# Nav_Solenoid_IO.net
KiCad netlist of a schematic drawn in Altium Designer
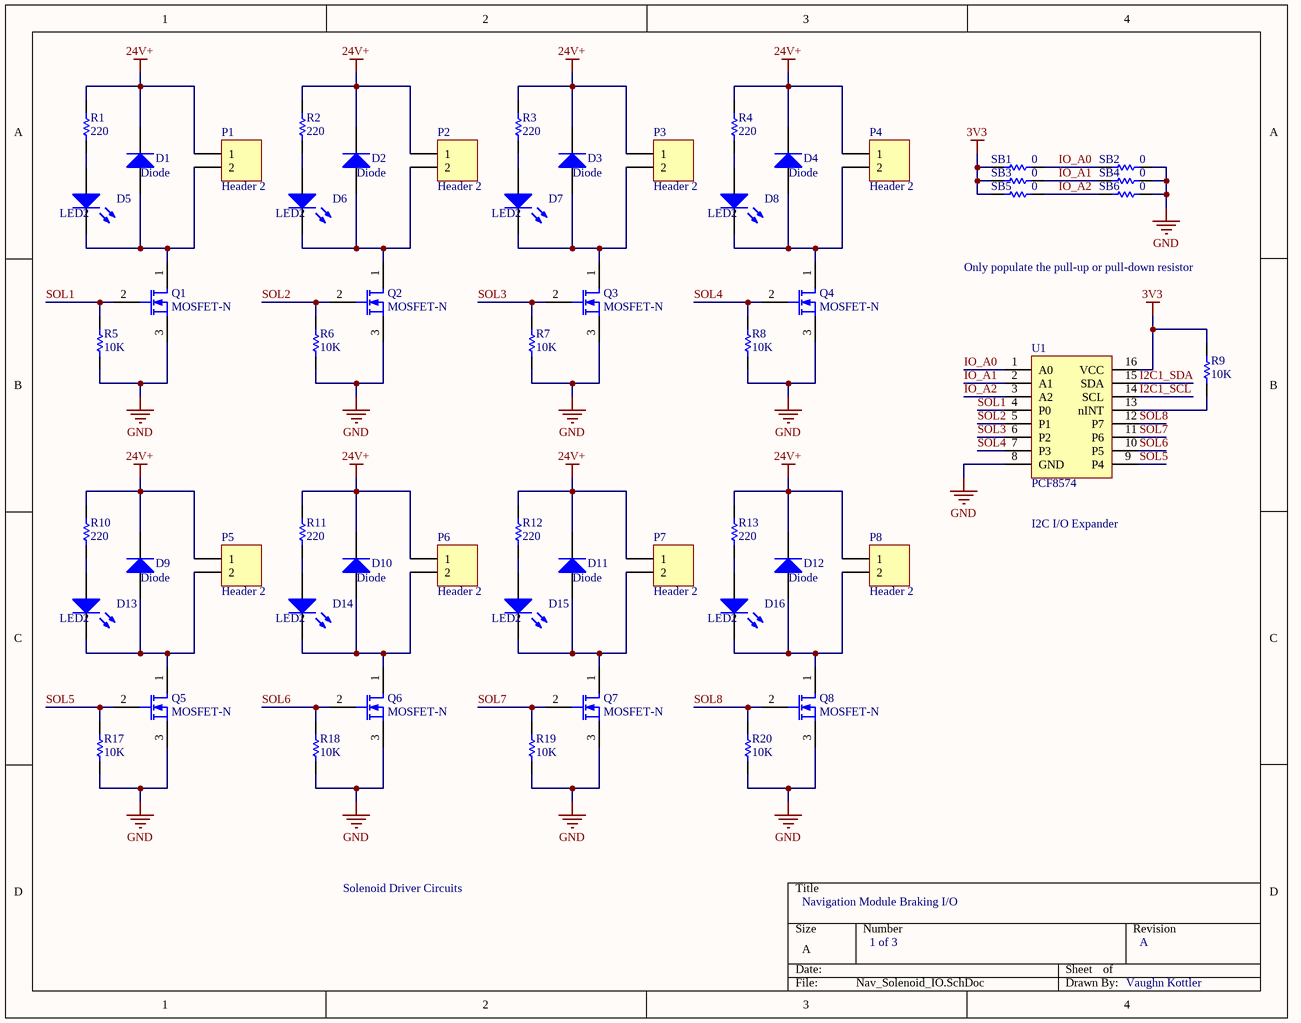
[diagram p0: Nav_Solenoid_IO.SchDoc]

(export (version "E")
  (design (tool "Eeschema 10.0.6"))
  (components
    (comp (ref "D1")
      (value "Diode")
      (footprint "DIODE_SMC")
      (description "Default Diode")
      (fields (field (name "PUBLISHER") "Altium Limited"))
      (libsource (lib "Miscellaneous Devices") (part "Diode"))
    )
    (comp (ref "D2")
      (value "Diode")
      (footprint "DIODE_SMC")
      (description "Default Diode")
      (fields (field (name "PUBLISHER") "Altium Limited"))
      (libsource (lib "Miscellaneous Devices") (part "Diode"))
    )
    (comp (ref "D3")
      (value "Diode")
      (footprint "DIODE_SMC")
      (description "Default Diode")
      (fields (field (name "PUBLISHER") "Altium Limited"))
      (libsource (lib "Miscellaneous Devices") (part "Diode"))
    )
    (comp (ref "D4")
      (value "Diode")
      (footprint "DIODE_SMC")
      (description "Default Diode")
      (fields (field (name "PUBLISHER") "Altium Limited"))
      (libsource (lib "Miscellaneous Devices") (part "Diode"))
    )
    (comp (ref "D5")
      (value "LED2")
      (footprint "3.2X1.6X1.1")
      (description "Typical RED, GREEN, YELLOW, AMBER GaAs LED")
      (fields (field (name "PUBLISHER") "Altium Limited"))
      (libsource (lib "Miscellaneous Devices") (part "LED2"))
    )
    (comp (ref "D6")
      (value "LED2")
      (footprint "3.2X1.6X1.1")
      (description "Typical RED, GREEN, YELLOW, AMBER GaAs LED")
      (fields (field (name "PUBLISHER") "Altium Limited"))
      (libsource (lib "Miscellaneous Devices") (part "LED2"))
    )
    (comp (ref "D7")
      (value "LED2")
      (footprint "3.2X1.6X1.1")
      (description "Typical RED, GREEN, YELLOW, AMBER GaAs LED")
      (fields (field (name "PUBLISHER") "Altium Limited"))
      (libsource (lib "Miscellaneous Devices") (part "LED2"))
    )
    (comp (ref "D8")
      (value "LED2")
      (footprint "3.2X1.6X1.1")
      (description "Typical RED, GREEN, YELLOW, AMBER GaAs LED")
      (fields (field (name "PUBLISHER") "Altium Limited"))
      (libsource (lib "Miscellaneous Devices") (part "LED2"))
    )
    (comp (ref "D9")
      (value "Diode")
      (footprint "DIODE_SMC")
      (description "Default Diode")
      (fields (field (name "PUBLISHER") "Altium Limited"))
      (libsource (lib "Miscellaneous Devices") (part "Diode"))
    )
    (comp (ref "D10")
      (value "Diode")
      (footprint "DIODE_SMC")
      (description "Default Diode")
      (fields (field (name "PUBLISHER") "Altium Limited"))
      (libsource (lib "Miscellaneous Devices") (part "Diode"))
    )
    (comp (ref "D11")
      (value "Diode")
      (footprint "DIODE_SMC")
      (description "Default Diode")
      (fields (field (name "PUBLISHER") "Altium Limited"))
      (libsource (lib "Miscellaneous Devices") (part "Diode"))
    )
    (comp (ref "D12")
      (value "Diode")
      (footprint "DIODE_SMC")
      (description "Default Diode")
      (fields (field (name "PUBLISHER") "Altium Limited"))
      (libsource (lib "Miscellaneous Devices") (part "Diode"))
    )
    (comp (ref "D13")
      (value "LED2")
      (footprint "3.2X1.6X1.1")
      (description "Typical RED, GREEN, YELLOW, AMBER GaAs LED")
      (fields (field (name "PUBLISHER") "Altium Limited"))
      (libsource (lib "Miscellaneous Devices") (part "LED2"))
    )
    (comp (ref "D14")
      (value "LED2")
      (footprint "3.2X1.6X1.1")
      (description "Typical RED, GREEN, YELLOW, AMBER GaAs LED")
      (fields (field (name "PUBLISHER") "Altium Limited"))
      (libsource (lib "Miscellaneous Devices") (part "LED2"))
    )
    (comp (ref "D15")
      (value "LED2")
      (footprint "3.2X1.6X1.1")
      (description "Typical RED, GREEN, YELLOW, AMBER GaAs LED")
      (fields (field (name "PUBLISHER") "Altium Limited"))
      (libsource (lib "Miscellaneous Devices") (part "LED2"))
    )
    (comp (ref "D16")
      (value "LED2")
      (footprint "3.2X1.6X1.1")
      (description "Typical RED, GREEN, YELLOW, AMBER GaAs LED")
      (fields (field (name "PUBLISHER") "Altium Limited"))
      (libsource (lib "Miscellaneous Devices") (part "LED2"))
    )
    (comp (ref "P1")
      (value "Header 2")
      (footprint "2POS TERM BLOCK")
      (description "Header, 2-Pin")
      (fields (field (name "PUBLISHER") "Altium Limited"))
      (libsource (lib "Miscellaneous Connectors") (part "Header 2"))
    )
    (comp (ref "P2")
      (value "Header 2")
      (footprint "2POS TERM BLOCK")
      (description "Header, 2-Pin")
      (fields (field (name "PUBLISHER") "Altium Limited"))
      (libsource (lib "Miscellaneous Connectors") (part "Header 2"))
    )
    (comp (ref "P3")
      (value "Header 2")
      (footprint "2POS TERM BLOCK")
      (description "Header, 2-Pin")
      (fields (field (name "PUBLISHER") "Altium Limited"))
      (libsource (lib "Miscellaneous Connectors") (part "Header 2"))
    )
    (comp (ref "P4")
      (value "Header 2")
      (footprint "2POS TERM BLOCK")
      (description "Header, 2-Pin")
      (fields (field (name "PUBLISHER") "Altium Limited"))
      (libsource (lib "Miscellaneous Connectors") (part "Header 2"))
    )
    (comp (ref "P5")
      (value "Header 2")
      (footprint "2POS TERM BLOCK")
      (description "Header, 2-Pin")
      (fields (field (name "PUBLISHER") "Altium Limited"))
      (libsource (lib "Miscellaneous Connectors") (part "Header 2"))
    )
    (comp (ref "P6")
      (value "Header 2")
      (footprint "2POS TERM BLOCK")
      (description "Header, 2-Pin")
      (fields (field (name "PUBLISHER") "Altium Limited"))
      (libsource (lib "Miscellaneous Connectors") (part "Header 2"))
    )
    (comp (ref "P7")
      (value "Header 2")
      (footprint "2POS TERM BLOCK")
      (description "Header, 2-Pin")
      (fields (field (name "PUBLISHER") "Altium Limited"))
      (libsource (lib "Miscellaneous Connectors") (part "Header 2"))
    )
    (comp (ref "P8")
      (value "Header 2")
      (footprint "2POS TERM BLOCK")
      (description "Header, 2-Pin")
      (fields (field (name "PUBLISHER") "Altium Limited"))
      (libsource (lib "Miscellaneous Connectors") (part "Header 2"))
    )
    (comp (ref "Q1")
      (value "MOSFET-N")
      (footprint "SOT23_N")
      (description "N-Channel MOSFET")
      (fields (field (name "PUBLISHER") "Altium Limited"))
      (libsource (lib "Miscellaneous Devices") (part "MOSFET-N"))
    )
    (comp (ref "Q2")
      (value "MOSFET-N")
      (footprint "SOT23_N")
      (description "N-Channel MOSFET")
      (fields (field (name "PUBLISHER") "Altium Limited"))
      (libsource (lib "Miscellaneous Devices") (part "MOSFET-N"))
    )
    (comp (ref "Q3")
      (value "MOSFET-N")
      (footprint "SOT23_N")
      (description "N-Channel MOSFET")
      (fields (field (name "PUBLISHER") "Altium Limited"))
      (libsource (lib "Miscellaneous Devices") (part "MOSFET-N"))
    )
    (comp (ref "Q4")
      (value "MOSFET-N")
      (footprint "SOT23_N")
      (description "N-Channel MOSFET")
      (fields (field (name "PUBLISHER") "Altium Limited"))
      (libsource (lib "Miscellaneous Devices") (part "MOSFET-N"))
    )
    (comp (ref "Q5")
      (value "MOSFET-N")
      (footprint "SOT23_N")
      (description "N-Channel MOSFET")
      (fields (field (name "PUBLISHER") "Altium Limited"))
      (libsource (lib "Miscellaneous Devices") (part "MOSFET-N"))
    )
    (comp (ref "Q6")
      (value "MOSFET-N")
      (footprint "SOT23_N")
      (description "N-Channel MOSFET")
      (fields (field (name "PUBLISHER") "Altium Limited"))
      (libsource (lib "Miscellaneous Devices") (part "MOSFET-N"))
    )
    (comp (ref "Q7")
      (value "MOSFET-N")
      (footprint "SOT23_N")
      (description "N-Channel MOSFET")
      (fields (field (name "PUBLISHER") "Altium Limited"))
      (libsource (lib "Miscellaneous Devices") (part "MOSFET-N"))
    )
    (comp (ref "Q8")
      (value "MOSFET-N")
      (footprint "SOT23_N")
      (description "N-Channel MOSFET")
      (fields (field (name "PUBLISHER") "Altium Limited"))
      (libsource (lib "Miscellaneous Devices") (part "MOSFET-N"))
    )
    (comp (ref "R1")
      (value "220")
      (footprint "6-0805_M")
      (description "Resistor")
      (fields (field (name "Comment") "Res1") (field (name "PUBLISHER") "Altium Limited"))
      (libsource (lib "Miscellaneous Devices") (part "Res1"))
    )
    (comp (ref "R2")
      (value "220")
      (footprint "6-0805_M")
      (description "Resistor")
      (fields (field (name "Comment") "Res1") (field (name "PUBLISHER") "Altium Limited"))
      (libsource (lib "Miscellaneous Devices") (part "Res1"))
    )
    (comp (ref "R3")
      (value "220")
      (footprint "6-0805_M")
      (description "Resistor")
      (fields (field (name "Comment") "Res1") (field (name "PUBLISHER") "Altium Limited"))
      (libsource (lib "Miscellaneous Devices") (part "Res1"))
    )
    (comp (ref "R4")
      (value "220")
      (footprint "6-0805_M")
      (description "Resistor")
      (fields (field (name "Comment") "Res1") (field (name "PUBLISHER") "Altium Limited"))
      (libsource (lib "Miscellaneous Devices") (part "Res1"))
    )
    (comp (ref "R5")
      (value "10K")
      (footprint "6-0805_M")
      (description "Resistor")
      (fields (field (name "Comment") "Res1") (field (name "PUBLISHER") "Altium Limited"))
      (libsource (lib "Miscellaneous Devices") (part "Res1"))
    )
    (comp (ref "R6")
      (value "10K")
      (footprint "6-0805_M")
      (description "Resistor")
      (fields (field (name "Comment") "Res1") (field (name "PUBLISHER") "Altium Limited"))
      (libsource (lib "Miscellaneous Devices") (part "Res1"))
    )
    (comp (ref "R7")
      (value "10K")
      (footprint "6-0805_M")
      (description "Resistor")
      (fields (field (name "Comment") "Res1") (field (name "PUBLISHER") "Altium Limited"))
      (libsource (lib "Miscellaneous Devices") (part "Res1"))
    )
    (comp (ref "R8")
      (value "10K")
      (footprint "6-0805_M")
      (description "Resistor")
      (fields (field (name "Comment") "Res1") (field (name "PUBLISHER") "Altium Limited"))
      (libsource (lib "Miscellaneous Devices") (part "Res1"))
    )
    (comp (ref "R9")
      (value "10K")
      (footprint "6-0805_M")
      (description "Resistor")
      (fields (field (name "Comment") "Res1") (field (name "PUBLISHER") "Altium Limited"))
      (libsource (lib "Miscellaneous Devices") (part "Res1"))
    )
    (comp (ref "R10")
      (value "220")
      (footprint "6-0805_M")
      (description "Resistor")
      (fields (field (name "Comment") "Res1") (field (name "PUBLISHER") "Altium Limited"))
      (libsource (lib "Miscellaneous Devices") (part "Res1"))
    )
    (comp (ref "R11")
      (value "220")
      (footprint "6-0805_M")
      (description "Resistor")
      (fields (field (name "Comment") "Res1") (field (name "PUBLISHER") "Altium Limited"))
      (libsource (lib "Miscellaneous Devices") (part "Res1"))
    )
    (comp (ref "R12")
      (value "220")
      (footprint "6-0805_M")
      (description "Resistor")
      (fields (field (name "Comment") "Res1") (field (name "PUBLISHER") "Altium Limited"))
      (libsource (lib "Miscellaneous Devices") (part "Res1"))
    )
    (comp (ref "R13")
      (value "220")
      (footprint "6-0805_M")
      (description "Resistor")
      (fields (field (name "Comment") "Res1") (field (name "PUBLISHER") "Altium Limited"))
      (libsource (lib "Miscellaneous Devices") (part "Res1"))
    )
    (comp (ref "R17")
      (value "10K")
      (footprint "6-0805_M")
      (description "Resistor")
      (fields (field (name "Comment") "Res1") (field (name "PUBLISHER") "Altium Limited"))
      (libsource (lib "Miscellaneous Devices") (part "Res1"))
    )
    (comp (ref "R18")
      (value "10K")
      (footprint "6-0805_M")
      (description "Resistor")
      (fields (field (name "Comment") "Res1") (field (name "PUBLISHER") "Altium Limited"))
      (libsource (lib "Miscellaneous Devices") (part "Res1"))
    )
    (comp (ref "R19")
      (value "10K")
      (footprint "6-0805_M")
      (description "Resistor")
      (fields (field (name "Comment") "Res1") (field (name "PUBLISHER") "Altium Limited"))
      (libsource (lib "Miscellaneous Devices") (part "Res1"))
    )
    (comp (ref "R20")
      (value "10K")
      (footprint "6-0805_M")
      (description "Resistor")
      (fields (field (name "Comment") "Res1") (field (name "PUBLISHER") "Altium Limited"))
      (libsource (lib "Miscellaneous Devices") (part "Res1"))
    )
    (comp (ref "SB1")
      (value "0")
      (footprint "6-0805_M")
      (description "Resistor")
      (fields (field (name "Comment") "Res1") (field (name "PUBLISHER") "Altium Limited"))
      (libsource (lib "Miscellaneous Devices") (part "Res1"))
    )
    (comp (ref "SB2")
      (value "0")
      (footprint "6-0805_M")
      (description "Resistor")
      (fields (field (name "Comment") "Res1") (field (name "PUBLISHER") "Altium Limited"))
      (libsource (lib "Miscellaneous Devices") (part "Res1"))
    )
    (comp (ref "SB3")
      (value "0")
      (footprint "6-0805_M")
      (description "Resistor")
      (fields (field (name "Comment") "Res1") (field (name "PUBLISHER") "Altium Limited"))
      (libsource (lib "Miscellaneous Devices") (part "Res1"))
    )
    (comp (ref "SB4")
      (value "0")
      (footprint "6-0805_M")
      (description "Resistor")
      (fields (field (name "Comment") "Res1") (field (name "PUBLISHER") "Altium Limited"))
      (libsource (lib "Miscellaneous Devices") (part "Res1"))
    )
    (comp (ref "SB5")
      (value "0")
      (footprint "6-0805_M")
      (description "Resistor")
      (fields (field (name "Comment") "Res1") (field (name "PUBLISHER") "Altium Limited"))
      (libsource (lib "Miscellaneous Devices") (part "Res1"))
    )
    (comp (ref "SB6")
      (value "0")
      (footprint "6-0805_M")
      (description "Resistor")
      (fields (field (name "Comment") "Res1") (field (name "PUBLISHER") "Altium Limited"))
      (libsource (lib "Miscellaneous Devices") (part "Res1"))
    )
    (comp (ref "U1")
      (value "PCF8574")
      (footprint "16-SOIC")
      (description "I2C I/O Expander")
      (libsource (lib "ic") (part "PCF8574"))
    )
  )
  (nets
    (net (code "1") (name "/I2C1_SCL") (class "Default")
      (node (ref "U1") (pin "14") (pinfunction "SCL_14") (pintype "passive"))
    )
    (net (code "2") (name "/I2C1_SDA") (class "Default")
      (node (ref "U1") (pin "15") (pinfunction "SDA_15") (pintype "passive"))
    )
    (net (code "3") (name "/IO_A0") (class "Default")
      (node (ref "SB1") (pin "1") (pinfunction "1_1") (pintype "passive"))
      (node (ref "SB2") (pin "2") (pinfunction "2_2") (pintype "passive"))
      (node (ref "U1") (pin "1") (pinfunction "A0_1") (pintype "passive"))
    )
    (net (code "4") (name "/IO_A1") (class "Default")
      (node (ref "SB3") (pin "1") (pinfunction "1_1") (pintype "passive"))
      (node (ref "SB4") (pin "2") (pinfunction "2_2") (pintype "passive"))
      (node (ref "U1") (pin "2") (pinfunction "A1_2") (pintype "passive"))
    )
    (net (code "5") (name "/IO_A2") (class "Default")
      (node (ref "SB5") (pin "1") (pinfunction "1_1") (pintype "passive"))
      (node (ref "SB6") (pin "2") (pinfunction "2_2") (pintype "passive"))
      (node (ref "U1") (pin "3") (pinfunction "A2_3") (pintype "passive"))
    )
    (net (code "6") (name "/SOL1") (class "Default")
      (node (ref "Q1") (pin "2") (pinfunction "G_2") (pintype "passive"))
      (node (ref "R5") (pin "2") (pinfunction "2_2") (pintype "passive"))
      (node (ref "U1") (pin "4") (pinfunction "P0_4") (pintype "passive"))
    )
    (net (code "7") (name "/SOL2") (class "Default")
      (node (ref "Q2") (pin "2") (pinfunction "G_2") (pintype "passive"))
      (node (ref "R6") (pin "2") (pinfunction "2_2") (pintype "passive"))
      (node (ref "U1") (pin "5") (pinfunction "P1_5") (pintype "passive"))
    )
    (net (code "8") (name "/SOL3") (class "Default")
      (node (ref "Q3") (pin "2") (pinfunction "G_2") (pintype "passive"))
      (node (ref "R7") (pin "2") (pinfunction "2_2") (pintype "passive"))
      (node (ref "U1") (pin "6") (pinfunction "P2_6") (pintype "passive"))
    )
    (net (code "9") (name "/SOL4") (class "Default")
      (node (ref "Q4") (pin "2") (pinfunction "G_2") (pintype "passive"))
      (node (ref "R8") (pin "2") (pinfunction "2_2") (pintype "passive"))
      (node (ref "U1") (pin "7") (pinfunction "P3_7") (pintype "passive"))
    )
    (net (code "10") (name "/SOL5") (class "Default")
      (node (ref "Q5") (pin "2") (pinfunction "G_2") (pintype "passive"))
      (node (ref "R17") (pin "2") (pinfunction "2_2") (pintype "passive"))
      (node (ref "U1") (pin "9") (pinfunction "P4_9") (pintype "passive"))
    )
    (net (code "11") (name "/SOL6") (class "Default")
      (node (ref "Q6") (pin "2") (pinfunction "G_2") (pintype "passive"))
      (node (ref "R18") (pin "2") (pinfunction "2_2") (pintype "passive"))
      (node (ref "U1") (pin "10") (pinfunction "P5_10") (pintype "passive"))
    )
    (net (code "12") (name "/SOL7") (class "Default")
      (node (ref "Q7") (pin "2") (pinfunction "G_2") (pintype "passive"))
      (node (ref "R19") (pin "2") (pinfunction "2_2") (pintype "passive"))
      (node (ref "U1") (pin "11") (pinfunction "P6_11") (pintype "passive"))
    )
    (net (code "13") (name "/SOL8") (class "Default")
      (node (ref "Q8") (pin "2") (pinfunction "G_2") (pintype "passive"))
      (node (ref "R20") (pin "2") (pinfunction "2_2") (pintype "passive"))
      (node (ref "U1") (pin "12") (pinfunction "P7_12") (pintype "passive"))
    )
    (net (code "14") (name "3V3") (class "Default")
      (node (ref "R9") (pin "2") (pinfunction "2_2") (pintype "passive"))
      (node (ref "SB1") (pin "2") (pinfunction "2_2") (pintype "passive"))
      (node (ref "SB3") (pin "2") (pinfunction "2_2") (pintype "passive"))
      (node (ref "SB5") (pin "2") (pinfunction "2_2") (pintype "passive"))
      (node (ref "U1") (pin "16") (pinfunction "VCC_16") (pintype "passive"))
    )
    (net (code "15") (name "24V+") (class "Default")
      (node (ref "D1") (pin "2") (pinfunction "K_2") (pintype "passive"))
      (node (ref "D10") (pin "2") (pinfunction "K_2") (pintype "passive"))
      (node (ref "D11") (pin "2") (pinfunction "K_2") (pintype "passive"))
      (node (ref "D12") (pin "2") (pinfunction "K_2") (pintype "passive"))
      (node (ref "D2") (pin "2") (pinfunction "K_2") (pintype "passive"))
      (node (ref "D3") (pin "2") (pinfunction "K_2") (pintype "passive"))
      (node (ref "D4") (pin "2") (pinfunction "K_2") (pintype "passive"))
      (node (ref "D9") (pin "2") (pinfunction "K_2") (pintype "passive"))
      (node (ref "P1") (pin "1") (pinfunction "1_1") (pintype "passive"))
      (node (ref "P2") (pin "1") (pinfunction "1_1") (pintype "passive"))
      (node (ref "P3") (pin "1") (pinfunction "1_1") (pintype "passive"))
      (node (ref "P4") (pin "1") (pinfunction "1_1") (pintype "passive"))
      (node (ref "P5") (pin "1") (pinfunction "1_1") (pintype "passive"))
      (node (ref "P6") (pin "1") (pinfunction "1_1") (pintype "passive"))
      (node (ref "P7") (pin "1") (pinfunction "1_1") (pintype "passive"))
      (node (ref "P8") (pin "1") (pinfunction "1_1") (pintype "passive"))
      (node (ref "R1") (pin "2") (pinfunction "2_2") (pintype "passive"))
      (node (ref "R10") (pin "2") (pinfunction "2_2") (pintype "passive"))
      (node (ref "R11") (pin "2") (pinfunction "2_2") (pintype "passive"))
      (node (ref "R12") (pin "2") (pinfunction "2_2") (pintype "passive"))
      (node (ref "R13") (pin "2") (pinfunction "2_2") (pintype "passive"))
      (node (ref "R2") (pin "2") (pinfunction "2_2") (pintype "passive"))
      (node (ref "R3") (pin "2") (pinfunction "2_2") (pintype "passive"))
      (node (ref "R4") (pin "2") (pinfunction "2_2") (pintype "passive"))
    )
    (net (code "16") (name "GND") (class "Default")
      (node (ref "Q1") (pin "3") (pinfunction "S_3") (pintype "passive"))
      (node (ref "Q2") (pin "3") (pinfunction "S_3") (pintype "passive"))
      (node (ref "Q3") (pin "3") (pinfunction "S_3") (pintype "passive"))
      (node (ref "Q4") (pin "3") (pinfunction "S_3") (pintype "passive"))
      (node (ref "Q5") (pin "3") (pinfunction "S_3") (pintype "passive"))
      (node (ref "Q6") (pin "3") (pinfunction "S_3") (pintype "passive"))
      (node (ref "Q7") (pin "3") (pinfunction "S_3") (pintype "passive"))
      (node (ref "Q8") (pin "3") (pinfunction "S_3") (pintype "passive"))
      (node (ref "R17") (pin "1") (pinfunction "1_1") (pintype "passive"))
      (node (ref "R18") (pin "1") (pinfunction "1_1") (pintype "passive"))
      (node (ref "R19") (pin "1") (pinfunction "1_1") (pintype "passive"))
      (node (ref "R20") (pin "1") (pinfunction "1_1") (pintype "passive"))
      (node (ref "R5") (pin "1") (pinfunction "1_1") (pintype "passive"))
      (node (ref "R6") (pin "1") (pinfunction "1_1") (pintype "passive"))
      (node (ref "R7") (pin "1") (pinfunction "1_1") (pintype "passive"))
      (node (ref "R8") (pin "1") (pinfunction "1_1") (pintype "passive"))
      (node (ref "SB2") (pin "1") (pinfunction "1_1") (pintype "passive"))
      (node (ref "SB4") (pin "1") (pinfunction "1_1") (pintype "passive"))
      (node (ref "SB6") (pin "1") (pinfunction "1_1") (pintype "passive"))
      (node (ref "U1") (pin "8") (pinfunction "GND_8") (pintype "passive"))
    )
    (net (code "17") (name "Net-(D1-A)") (class "Default")
      (node (ref "D1") (pin "1") (pinfunction "A_1") (pintype "passive"))
      (node (ref "D5") (pin "2") (pinfunction "K_2") (pintype "passive"))
      (node (ref "P1") (pin "2") (pinfunction "2_2") (pintype "passive"))
      (node (ref "Q1") (pin "1") (pinfunction "D_1") (pintype "passive"))
    )
    (net (code "18") (name "Net-(D2-A)") (class "Default")
      (node (ref "D2") (pin "1") (pinfunction "A_1") (pintype "passive"))
      (node (ref "D6") (pin "2") (pinfunction "K_2") (pintype "passive"))
      (node (ref "P2") (pin "2") (pinfunction "2_2") (pintype "passive"))
      (node (ref "Q2") (pin "1") (pinfunction "D_1") (pintype "passive"))
    )
    (net (code "19") (name "Net-(D3-A)") (class "Default")
      (node (ref "D3") (pin "1") (pinfunction "A_1") (pintype "passive"))
      (node (ref "D7") (pin "2") (pinfunction "K_2") (pintype "passive"))
      (node (ref "P3") (pin "2") (pinfunction "2_2") (pintype "passive"))
      (node (ref "Q3") (pin "1") (pinfunction "D_1") (pintype "passive"))
    )
    (net (code "20") (name "Net-(D4-A)") (class "Default")
      (node (ref "D4") (pin "1") (pinfunction "A_1") (pintype "passive"))
      (node (ref "D8") (pin "2") (pinfunction "K_2") (pintype "passive"))
      (node (ref "P4") (pin "2") (pinfunction "2_2") (pintype "passive"))
      (node (ref "Q4") (pin "1") (pinfunction "D_1") (pintype "passive"))
    )
    (net (code "21") (name "Net-(D5-A)") (class "Default")
      (node (ref "D5") (pin "1") (pinfunction "A_1") (pintype "passive"))
      (node (ref "R1") (pin "1") (pinfunction "1_1") (pintype "passive"))
    )
    (net (code "22") (name "Net-(D6-A)") (class "Default")
      (node (ref "D6") (pin "1") (pinfunction "A_1") (pintype "passive"))
      (node (ref "R2") (pin "1") (pinfunction "1_1") (pintype "passive"))
    )
    (net (code "23") (name "Net-(D7-A)") (class "Default")
      (node (ref "D7") (pin "1") (pinfunction "A_1") (pintype "passive"))
      (node (ref "R3") (pin "1") (pinfunction "1_1") (pintype "passive"))
    )
    (net (code "24") (name "Net-(D8-A)") (class "Default")
      (node (ref "D8") (pin "1") (pinfunction "A_1") (pintype "passive"))
      (node (ref "R4") (pin "1") (pinfunction "1_1") (pintype "passive"))
    )
    (net (code "25") (name "Net-(D10-A)") (class "Default")
      (node (ref "D10") (pin "1") (pinfunction "A_1") (pintype "passive"))
      (node (ref "D14") (pin "2") (pinfunction "K_2") (pintype "passive"))
      (node (ref "P6") (pin "2") (pinfunction "2_2") (pintype "passive"))
      (node (ref "Q6") (pin "1") (pinfunction "D_1") (pintype "passive"))
    )
    (net (code "26") (name "Net-(D11-A)") (class "Default")
      (node (ref "D11") (pin "1") (pinfunction "A_1") (pintype "passive"))
      (node (ref "D15") (pin "2") (pinfunction "K_2") (pintype "passive"))
      (node (ref "P7") (pin "2") (pinfunction "2_2") (pintype "passive"))
      (node (ref "Q7") (pin "1") (pinfunction "D_1") (pintype "passive"))
    )
    (net (code "27") (name "Net-(D12-A)") (class "Default")
      (node (ref "D12") (pin "1") (pinfunction "A_1") (pintype "passive"))
      (node (ref "D16") (pin "2") (pinfunction "K_2") (pintype "passive"))
      (node (ref "P8") (pin "2") (pinfunction "2_2") (pintype "passive"))
      (node (ref "Q8") (pin "1") (pinfunction "D_1") (pintype "passive"))
    )
    (net (code "28") (name "Net-(D13-A)") (class "Default")
      (node (ref "D13") (pin "1") (pinfunction "A_1") (pintype "passive"))
      (node (ref "R10") (pin "1") (pinfunction "1_1") (pintype "passive"))
    )
    (net (code "29") (name "Net-(D13-K)") (class "Default")
      (node (ref "D13") (pin "2") (pinfunction "K_2") (pintype "passive"))
      (node (ref "D9") (pin "1") (pinfunction "A_1") (pintype "passive"))
      (node (ref "P5") (pin "2") (pinfunction "2_2") (pintype "passive"))
      (node (ref "Q5") (pin "1") (pinfunction "D_1") (pintype "passive"))
    )
    (net (code "30") (name "Net-(D14-A)") (class "Default")
      (node (ref "D14") (pin "1") (pinfunction "A_1") (pintype "passive"))
      (node (ref "R11") (pin "1") (pinfunction "1_1") (pintype "passive"))
    )
    (net (code "31") (name "Net-(D15-A)") (class "Default")
      (node (ref "D15") (pin "1") (pinfunction "A_1") (pintype "passive"))
      (node (ref "R12") (pin "1") (pinfunction "1_1") (pintype "passive"))
    )
    (net (code "32") (name "Net-(D16-A)") (class "Default")
      (node (ref "D16") (pin "1") (pinfunction "A_1") (pintype "passive"))
      (node (ref "R13") (pin "1") (pinfunction "1_1") (pintype "passive"))
    )
    (net (code "33") (name "Net-(U1-nINT)") (class "Default")
      (node (ref "R9") (pin "1") (pinfunction "1_1") (pintype "passive"))
      (node (ref "U1") (pin "13") (pinfunction "nINT_13") (pintype "passive"))
    )
  )
)
